# BigClown_Sensor_adapter_v0_3.net
KiCad netlist of a schematic drawn in EAGLE
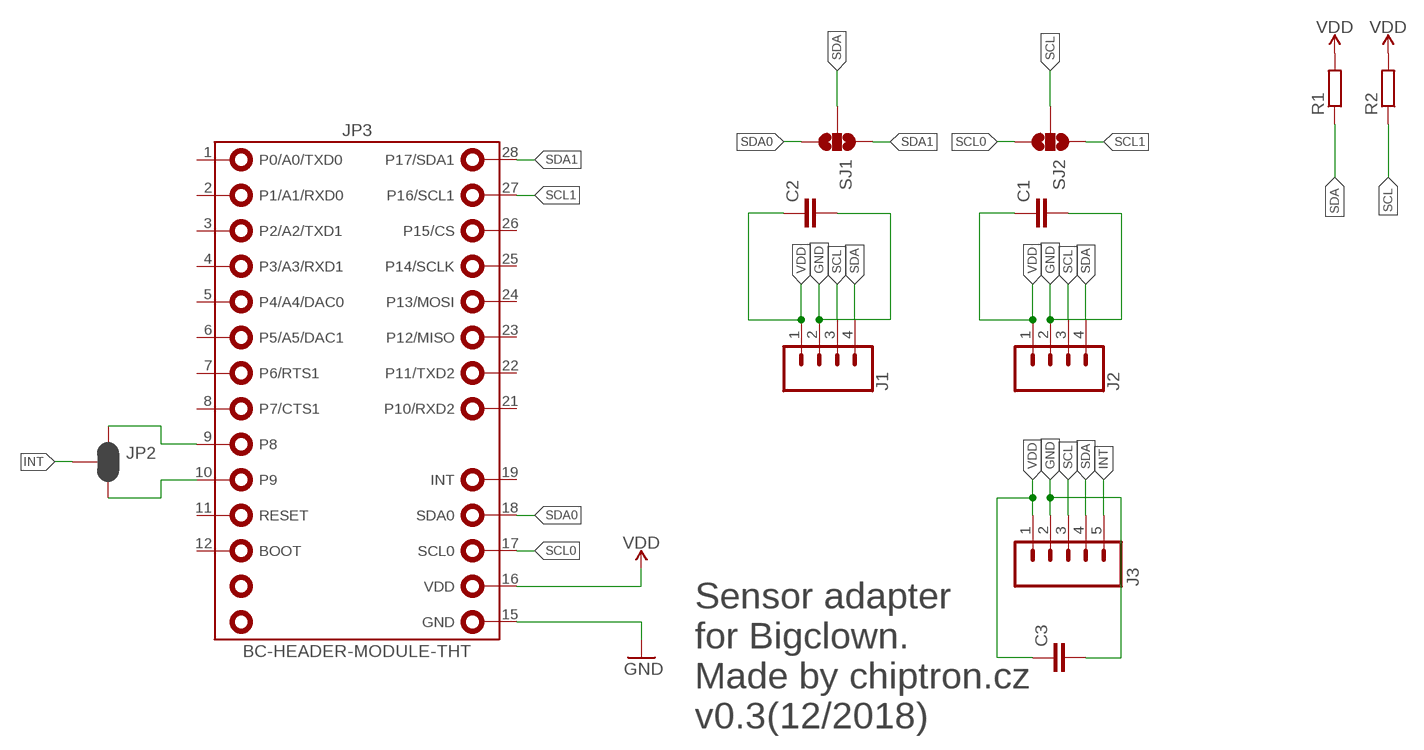
[diagram p0: schematic, sheet 1]

(export (version "E")
  (design (tool "Eeschema 10.0.6"))
  (components
    (comp (ref "C1")
      (value "C-EUC0805")
      (footprint "eagle-import:C0805")
      (libsource (lib "eagle-import") (part "C-EUC0805"))
    )
    (comp (ref "C2")
      (value "C-EUC0805")
      (footprint "eagle-import:C0805")
      (libsource (lib "eagle-import") (part "C-EUC0805"))
    )
    (comp (ref "C3")
      (value "C-EUC0805")
      (footprint "eagle-import:C0805")
      (libsource (lib "eagle-import") (part "C-EUC0805"))
    )
    (comp (ref "J1")
      (value "CONN_04LONGPADS")
      (footprint "eagle-import:1X04_LONGPADS")
      (libsource (lib "eagle-import") (part "CONN_04LONGPADS"))
    )
    (comp (ref "J2")
      (value "CONN_04LONGPADS")
      (footprint "eagle-import:1X04_LONGPADS")
      (libsource (lib "eagle-import") (part "CONN_04LONGPADS"))
    )
    (comp (ref "J3")
      (value "M05PTH_LONGPADS")
      (footprint "eagle-import:1X05_LONGPADS")
      (libsource (lib "eagle-import") (part "M05PTH_LONGPADS"))
    )
    (comp (ref "JP2")
      (value "JUMPER-SMT_3_2-NC_PASTE_SILK")
      (footprint "eagle-import:SMT-JUMPER_3_2-NC_PASTE_SILK")
      (libsource (lib "eagle-import") (part "JUMPER-SMT_3_2-NC_PASTE_SILK"))
    )
    (comp (ref "JP3")
      (value "BC-HEADER-MODULE-THT")
      (footprint "eagle-import:BC-HEADER-MODULE-THT")
      (libsource (lib "eagle-import") (part "BC-HEADER-MODULE-THT"))
    )
    (comp (ref "R1")
      (value "R-EU_M0805")
      (footprint "eagle-import:M0805")
      (libsource (lib "eagle-import") (part "R-EU_M0805"))
    )
    (comp (ref "R2")
      (value "R-EU_M0805")
      (footprint "eagle-import:M0805")
      (libsource (lib "eagle-import") (part "R-EU_M0805"))
    )
    (comp (ref "SJ1")
      (value "SOLDERJUMPER_2WAYS")
      (footprint "eagle-import:SJ_3")
      (libsource (lib "eagle-import") (part "SOLDERJUMPER_2WAYS"))
    )
    (comp (ref "SJ2")
      (value "SOLDERJUMPER_2WAYS")
      (footprint "eagle-import:SJ_3")
      (libsource (lib "eagle-import") (part "SOLDERJUMPER_2WAYS"))
    )
  )
  (nets
    (net (code "1") (name "GND") (class "Default")
      (node (ref "C1") (pin "2") (pinfunction "2_2") (pintype "passive"))
      (node (ref "C2") (pin "2") (pinfunction "2_2") (pintype "passive"))
      (node (ref "C3") (pin "2") (pinfunction "2_2") (pintype "passive"))
      (node (ref "J1") (pin "2") (pinfunction "2_2") (pintype "passive"))
      (node (ref "J2") (pin "2") (pinfunction "2_2") (pintype "passive"))
      (node (ref "J3") (pin "2") (pinfunction "2_2") (pintype "passive"))
      (node (ref "JP3") (pin "15") (pinfunction "GND_15") (pintype "passive"))
    )
    (net (code "2") (name "INT") (class "Default")
      (node (ref "J3") (pin "5") (pinfunction "5_5") (pintype "passive"))
      (node (ref "JP2") (pin "2") (pinfunction "2_2") (pintype "passive"))
    )
    (net (code "3") (name "Net-(JP3-P8)") (class "Default")
      (node (ref "JP2") (pin "1") (pinfunction "1_1") (pintype "passive"))
      (node (ref "JP3") (pin "9") (pinfunction "P8_9") (pintype "passive"))
    )
    (net (code "4") (name "Net-(JP3-P9)") (class "Default")
      (node (ref "JP2") (pin "3") (pinfunction "3_3") (pintype "passive"))
      (node (ref "JP3") (pin "10") (pinfunction "P9_10") (pintype "passive"))
    )
    (net (code "5") (name "SCL") (class "Default")
      (node (ref "J1") (pin "3") (pinfunction "3_3") (pintype "passive"))
      (node (ref "J2") (pin "3") (pinfunction "3_3") (pintype "passive"))
      (node (ref "J3") (pin "3") (pinfunction "3_3") (pintype "passive"))
      (node (ref "R2") (pin "1") (pinfunction "1_1") (pintype "passive"))
      (node (ref "SJ2") (pin "2") (pinfunction "2_2") (pintype "passive"))
    )
    (net (code "6") (name "SCL0") (class "Default")
      (node (ref "JP3") (pin "17") (pinfunction "SCL0_17") (pintype "passive"))
      (node (ref "SJ2") (pin "3") (pinfunction "3_3") (pintype "passive"))
    )
    (net (code "7") (name "SCL1") (class "Default")
      (node (ref "JP3") (pin "27") (pinfunction "P16/SCL1_27") (pintype "passive"))
      (node (ref "SJ2") (pin "1") (pinfunction "1_1") (pintype "passive"))
    )
    (net (code "8") (name "SDA") (class "Default")
      (node (ref "J1") (pin "4") (pinfunction "4_4") (pintype "passive"))
      (node (ref "J2") (pin "4") (pinfunction "4_4") (pintype "passive"))
      (node (ref "J3") (pin "4") (pinfunction "4_4") (pintype "passive"))
      (node (ref "R1") (pin "1") (pinfunction "1_1") (pintype "passive"))
      (node (ref "SJ1") (pin "2") (pinfunction "2_2") (pintype "passive"))
    )
    (net (code "9") (name "SDA0") (class "Default")
      (node (ref "JP3") (pin "18") (pinfunction "SDA0_18") (pintype "passive"))
      (node (ref "SJ1") (pin "3") (pinfunction "3_3") (pintype "passive"))
    )
    (net (code "10") (name "SDA1") (class "Default")
      (node (ref "JP3") (pin "28") (pinfunction "P17/SDA1_28") (pintype "passive"))
      (node (ref "SJ1") (pin "1") (pinfunction "1_1") (pintype "passive"))
    )
    (net (code "11") (name "VDD") (class "Default")
      (node (ref "C1") (pin "1") (pinfunction "1_1") (pintype "passive"))
      (node (ref "C2") (pin "1") (pinfunction "1_1") (pintype "passive"))
      (node (ref "C3") (pin "1") (pinfunction "1_1") (pintype "passive"))
      (node (ref "J1") (pin "1") (pinfunction "1_1") (pintype "passive"))
      (node (ref "J2") (pin "1") (pinfunction "1_1") (pintype "passive"))
      (node (ref "J3") (pin "1") (pinfunction "1_1") (pintype "passive"))
      (node (ref "JP3") (pin "16") (pinfunction "VDD_16") (pintype "passive"))
      (node (ref "R1") (pin "2") (pinfunction "2_2") (pintype "passive"))
      (node (ref "R2") (pin "2") (pinfunction "2_2") (pintype "passive"))
    )
    (net (code "12") (name "unconnected-(JP3-BOOT-Pad12)") (class "Default")
      (node (ref "JP3") (pin "12") (pinfunction "BOOT_12") (pintype "passive"))
    )
    (net (code "13") (name "unconnected-(JP3-INT-Pad19)") (class "Default")
      (node (ref "JP3") (pin "19") (pinfunction "INT_19") (pintype "passive"))
    )
    (net (code "14") (name "unconnected-(JP3-P0{slash}A0{slash}TXD0-Pad1)") (class "Default")
      (node (ref "JP3") (pin "1") (pinfunction "P0/A0/TXD0_1") (pintype "passive"))
    )
    (net (code "15") (name "unconnected-(JP3-P1{slash}A1{slash}RXD03-Pad2)") (class "Default")
      (node (ref "JP3") (pin "2") (pinfunction "P1/A1/RXD03_2") (pintype "passive"))
    )
    (net (code "16") (name "unconnected-(JP3-P2{slash}A2{slash}TXD1-Pad3)") (class "Default")
      (node (ref "JP3") (pin "3") (pinfunction "P2/A2/TXD1_3") (pintype "passive"))
    )
    (net (code "17") (name "unconnected-(JP3-P3{slash}A3{slash}RXD1-Pad4)") (class "Default")
      (node (ref "JP3") (pin "4") (pinfunction "P3/A3/RXD1_4") (pintype "passive"))
    )
    (net (code "18") (name "unconnected-(JP3-P4{slash}A4{slash}DAC0-Pad5)") (class "Default")
      (node (ref "JP3") (pin "5") (pinfunction "P4/A4/DAC0_5") (pintype "passive"))
    )
    (net (code "19") (name "unconnected-(JP3-P5{slash}A5{slash}DAC1-Pad6)") (class "Default")
      (node (ref "JP3") (pin "6") (pinfunction "P5/A5/DAC1_6") (pintype "passive"))
    )
    (net (code "20") (name "unconnected-(JP3-P6{slash}RTS1-Pad7)") (class "Default")
      (node (ref "JP3") (pin "7") (pinfunction "P6/RTS1_7") (pintype "passive"))
    )
    (net (code "21") (name "unconnected-(JP3-P7{slash}CTS1-Pad8)") (class "Default")
      (node (ref "JP3") (pin "8") (pinfunction "P7/CTS1_8") (pintype "passive"))
    )
    (net (code "22") (name "unconnected-(JP3-P10{slash}RXD2-Pad21)") (class "Default")
      (node (ref "JP3") (pin "21") (pinfunction "P10/RXD2_21") (pintype "passive"))
    )
    (net (code "23") (name "unconnected-(JP3-P11{slash}TXD2-Pad22)") (class "Default")
      (node (ref "JP3") (pin "22") (pinfunction "P11/TXD2_22") (pintype "passive"))
    )
    (net (code "24") (name "unconnected-(JP3-P12{slash}MISO-Pad23)") (class "Default")
      (node (ref "JP3") (pin "23") (pinfunction "P12/MISO_23") (pintype "passive"))
    )
    (net (code "25") (name "unconnected-(JP3-P13{slash}MOSI-Pad24)") (class "Default")
      (node (ref "JP3") (pin "24") (pinfunction "P13/MOSI_24") (pintype "passive"))
    )
    (net (code "26") (name "unconnected-(JP3-P14{slash}SCLK-Pad25)") (class "Default")
      (node (ref "JP3") (pin "25") (pinfunction "P14/SCLK_25") (pintype "passive"))
    )
    (net (code "27") (name "unconnected-(JP3-P15{slash}CS-Pad26)") (class "Default")
      (node (ref "JP3") (pin "26") (pinfunction "P15/CS_26") (pintype "passive"))
    )
    (net (code "28") (name "unconnected-(JP3-RESET-Pad11)") (class "Default")
      (node (ref "JP3") (pin "11") (pinfunction "RESET_11") (pintype "passive"))
    )
  )
)
